# GPS.net
KiCad netlist of a schematic drawn in Altium Designer
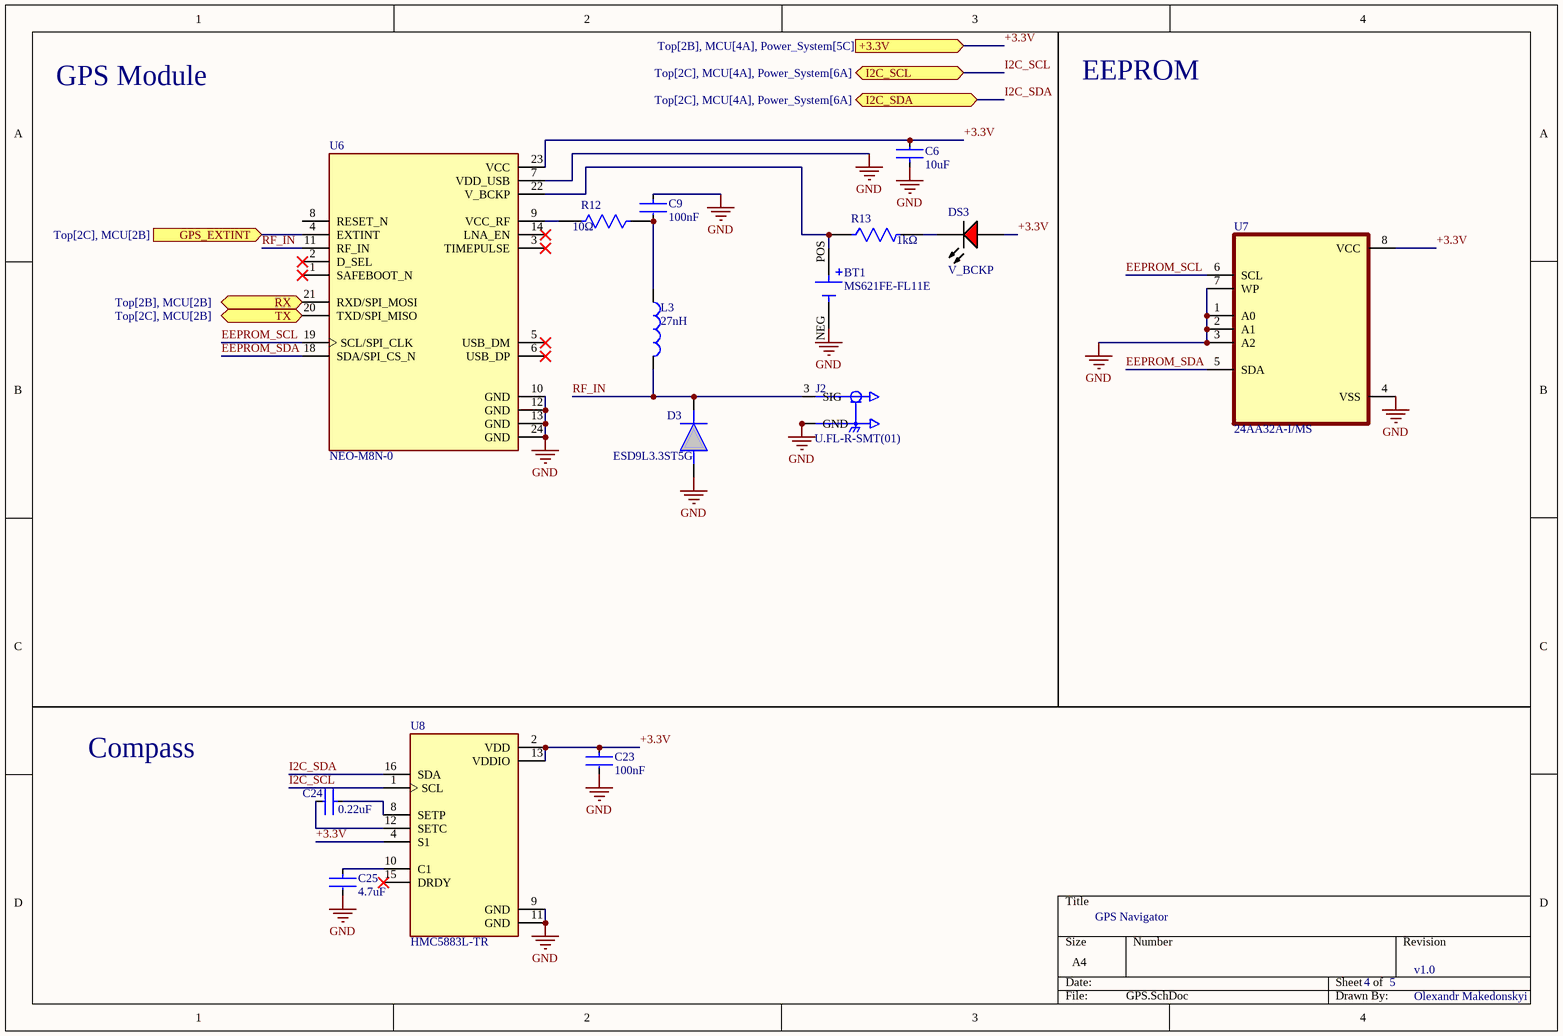
[diagram p0: GPS.SchDoc]

(export (version "E")
  (design (tool "Eeschema 10.0.6"))
  (components
    (comp (ref "BT1")
      (value "MS621FE-FL11E")
      (footprint "gps_project_pcb_library:BAT_MS621FE-FL11E")
      (description "Coin, 6.8mm 3 V Lithium Battery Rechargeable (Secondary) 5.5mAh")
      (fields (field (name "MF") "Seiko Instruments"))
      (libsource (lib "gps_project_schematic_library") (part "MS621FE-FL11E"))
    )
    (comp (ref "C6")
      (value "10uF")
      (footprint "0603_CAPACITOR")
      (libsource (lib "Olexandr Makedonskyi") (part "CAPACITOR"))
    )
    (comp (ref "C9")
      (value "100nF")
      (footprint "0603_CAPACITOR")
      (libsource (lib "Olexandr Makedonskyi") (part "CAPACITOR"))
    )
    (comp (ref "C23")
      (value "100nF")
      (footprint "0402_CAPACITOR")
      (libsource (lib "Olexandr Makedonskyi") (part "CAPACITOR"))
    )
    (comp (ref "C24")
      (value "0.22uF")
      (footprint "0402_CAPACITOR")
      (libsource (lib "Olexandr Makedonskyi") (part "CAPACITOR"))
    )
    (comp (ref "C25")
      (value "4.7uF")
      (footprint "0402_CAPACITOR")
      (libsource (lib "Olexandr Makedonskyi") (part "CAPACITOR"))
    )
    (comp (ref "D3")
      (value "ESD9L3.3ST5G")
      (footprint "gps_project_pcb_library:DIOM1006X40N")
      (description "Transient Voltage Suppressors ESD Protection Diodes with UltraLow Capacitance")
      (fields (field (name "MOUSER PART NUMBER") "863-ESD9L3.3ST5G"))
      (libsource (lib "gps_project_schematic_library") (part "ESD9L3.3ST5G"))
    )
    (comp (ref "DS3")
      (value "V_BCKP")
      (footprint "gps_project_pcb_library:RED_LED_1206")
      (description "LED Red, 65 mW, -40 to 85 degC, 2-Pin SMD, RoHS, Tape and Reel")
      (fields (field (name "MANUFACTURER") "Lumex") (field (name "PART NO") "SML-LX1206IC-TR"))
      (libsource (lib "gps_project_schematic_library") (part "LED_RED_1206"))
    )
    (comp (ref "J2")
      (value "U.FL-R-SMT(01)")
      (footprint "gps_project_pcb_library:HRS_U.FL-R-SMT(01)")
      (fields (field (name "MF") "Hirose"))
      (libsource (lib "gps_project_schematic_library") (part "U.FL-R-SMT(01)"))
    )
    (comp (ref "L3")
      (value "27nH")
      (footprint "gps_project_pcb_library:27nH")
      (description "Inductor with Inductance: 27nH Tol. +/-5%, Package: 0402 _1005_")
      (fields (field (name "MP") "LQG15HS27NJ02D") (field (name "MF") "Murata"))
      (libsource (lib "gps_project_schematic_library") (part "27nH"))
    )
    (comp (ref "R12")
      (value "10Ω")
      (footprint "1206_RESISTOR")
      (libsource (lib "gps_project_schematic_library") (part "RESISTOR"))
    )
    (comp (ref "R13")
      (value "1kΩ")
      (footprint "gps_project_pcb_library:0603_RESISTOR")
      (fields (field (name "Comment") "RESISTOR"))
      (libsource (lib "gps_project_schematic_library") (part "RESISTOR"))
    )
    (comp (ref "U6")
      (value "NEO-M8N-0")
      (footprint "gps_project_pcb_library:XCVR_NEO-M8N-0")
      (description "series RF Receiver BeiDou, Galileo, GLONASS, GNSS, GPS 1.575GHz -167dBm - - -")
      (fields (field (name "MF") "U-Blox America"))
      (libsource (lib "gps_project_schematic_library") (part "NEO-M8N-0"))
    )
    (comp (ref "U7")
      (value "24AA32A-I/MS")
      (footprint "gps_project_pcb_library:SOP65P490X110-8N (memory)")
      (description "32K, 4K X 8 1.8V SERIAL EE IND ¦ Microchip Technology Inc. 24AA32A-I/MS")
      (fields (field (name "MF") "Microchip"))
      (libsource (lib "gps_project_schematic_library") (part "24AA32A-I/MS"))
    )
    (comp (ref "U8")
      (value "HMC5883L-TR")
      (footprint "gps_project_pcb_library:XDCR_HMC5883L-TR")
      (fields (field (name "MF") "STMicroelectronics") (field (name "MP") "HMC5883LTR"))
      (libsource (lib "gps_project_schematic_library") (part "HMC5883L-TR"))
    )
  )
  (nets
    (net (code "1") (name "/+3.3V") (class "Default")
      (node (ref "C23") (pin "1") (pinfunction "1_1") (pintype "passive"))
      (node (ref "C6") (pin "2") (pinfunction "2_2") (pintype "passive"))
      (node (ref "DS3") (pin "1") (pinfunction "A_1") (pintype "passive"))
      (node (ref "U6") (pin "23") (pinfunction "VCC_23") (pintype "passive"))
      (node (ref "U7") (pin "8") (pinfunction "VCC_8") (pintype "passive"))
      (node (ref "U8") (pin "13") (pinfunction "VDDIO_13") (pintype "passive"))
      (node (ref "U8") (pin "2") (pinfunction "VDD_2") (pintype "passive"))
      (node (ref "U8") (pin "4") (pinfunction "S1_4") (pintype "passive"))
    )
    (net (code "2") (name "/EEPROM_SCL") (class "Default")
      (node (ref "U6") (pin "19") (pinfunction "SCL/SPI_CLK_19") (pintype "passive"))
      (node (ref "U7") (pin "6") (pinfunction "SCL_6") (pintype "passive"))
    )
    (net (code "3") (name "/EEPROM_SDA") (class "Default")
      (node (ref "U6") (pin "18") (pinfunction "SDA/SPI_CS_N_18") (pintype "passive"))
      (node (ref "U7") (pin "5") (pinfunction "SDA_5") (pintype "passive"))
    )
    (net (code "4") (name "/GPS_EXTINT") (class "Default")
      (node (ref "U6") (pin "4") (pinfunction "EXTINT_4") (pintype "passive"))
    )
    (net (code "5") (name "/I2C_SCL") (class "Default")
      (node (ref "U8") (pin "1") (pinfunction "SCL_1") (pintype "passive"))
    )
    (net (code "6") (name "/I2C_SDA") (class "Default")
      (node (ref "U8") (pin "16") (pinfunction "SDA_16") (pintype "passive"))
    )
    (net (code "7") (name "/RF_IN") (class "Default")
      (node (ref "D3") (pin "1") (pinfunction "K_1") (pintype "passive"))
      (node (ref "J2") (pin "3") (pinfunction "SIG_3") (pintype "passive"))
      (node (ref "L3") (pin "2") (pinfunction "2_2") (pintype "passive"))
      (node (ref "U6") (pin "11") (pinfunction "RF_IN_11") (pintype "passive"))
    )
    (net (code "8") (name "/RX") (class "Default")
      (node (ref "U6") (pin "21") (pinfunction "RXD/SPI_MOSI_21") (pintype "passive"))
    )
    (net (code "9") (name "/TX") (class "Default")
      (node (ref "U6") (pin "20") (pinfunction "TXD/SPI_MISO_20") (pintype "passive"))
    )
    (net (code "10") (name "GND") (class "Default")
      (node (ref "BT1") (pin "NEG") (pinfunction "NEG_NEG") (pintype "passive"))
      (node (ref "C23") (pin "2") (pinfunction "2_2") (pintype "passive"))
      (node (ref "C25") (pin "2") (pinfunction "2_2") (pintype "passive"))
      (node (ref "C6") (pin "1") (pinfunction "1_1") (pintype "passive"))
      (node (ref "C9") (pin "1") (pinfunction "1_1") (pintype "passive"))
      (node (ref "D3") (pin "2") (pinfunction "A_2") (pintype "passive"))
      (node (ref "J2") (pin "1") (pinfunction "GND_1") (pintype "passive"))
      (node (ref "J2") (pin "2") (pinfunction "GND_2") (pintype "passive"))
      (node (ref "U6") (pin "10") (pinfunction "GND_10") (pintype "passive"))
      (node (ref "U6") (pin "12") (pinfunction "GND_12") (pintype "passive"))
      (node (ref "U6") (pin "13") (pinfunction "GND_13") (pintype "passive"))
      (node (ref "U6") (pin "24") (pinfunction "GND_24") (pintype "passive"))
      (node (ref "U6") (pin "7") (pinfunction "VDD_USB_7") (pintype "passive"))
      (node (ref "U7") (pin "1") (pinfunction "A0_1") (pintype "passive"))
      (node (ref "U7") (pin "2") (pinfunction "A1_2") (pintype "passive"))
      (node (ref "U7") (pin "3") (pinfunction "A2_3") (pintype "passive"))
      (node (ref "U7") (pin "4") (pinfunction "VSS_4") (pintype "passive"))
      (node (ref "U7") (pin "7") (pinfunction "WP_7") (pintype "passive"))
      (node (ref "U8") (pin "11") (pinfunction "GND_11") (pintype "passive"))
      (node (ref "U8") (pin "9") (pinfunction "GND_9") (pintype "passive"))
    )
    (net (code "11") (name "Net-(C9-Pad2)") (class "Default")
      (node (ref "C9") (pin "2") (pinfunction "2_2") (pintype "passive"))
      (node (ref "L3") (pin "1") (pinfunction "1_1") (pintype "passive"))
      (node (ref "R12") (pin "1") (pinfunction "1_1") (pintype "passive"))
    )
    (net (code "12") (name "Net-(DS3-K)") (class "Default")
      (node (ref "DS3") (pin "2") (pinfunction "K_2") (pintype "passive"))
      (node (ref "R13") (pin "2") (pinfunction "2_2") (pintype "passive"))
    )
    (net (code "13") (name "Net-(U6-VCC_RF)") (class "Default")
      (node (ref "R12") (pin "2") (pinfunction "2_2") (pintype "passive"))
      (node (ref "U6") (pin "9") (pinfunction "VCC_RF_9") (pintype "passive"))
    )
    (net (code "14") (name "Net-(U6-V_BCKP)") (class "Default")
      (node (ref "BT1") (pin "POS") (pinfunction "POS_POS") (pintype "passive"))
      (node (ref "R13") (pin "1") (pinfunction "1_1") (pintype "passive"))
      (node (ref "U6") (pin "22") (pinfunction "V_BCKP_22") (pintype "passive"))
    )
    (net (code "15") (name "Net-(U8-C1)") (class "Default")
      (node (ref "C25") (pin "1") (pinfunction "1_1") (pintype "passive"))
      (node (ref "U8") (pin "10") (pinfunction "C1_10") (pintype "passive"))
    )
    (net (code "16") (name "Net-(U8-SETC)") (class "Default")
      (node (ref "C24") (pin "2") (pinfunction "2_2") (pintype "passive"))
      (node (ref "U8") (pin "12") (pinfunction "SETC_12") (pintype "passive"))
    )
    (net (code "17") (name "Net-(U8-SETP)") (class "Default")
      (node (ref "C24") (pin "1") (pinfunction "1_1") (pintype "passive"))
      (node (ref "U8") (pin "8") (pinfunction "SETP_8") (pintype "passive"))
    )
    (net (code "18") (name "unconnected-(U6-D_SEL-Pad2)") (class "Default")
      (node (ref "U6") (pin "2") (pinfunction "D_SEL_2") (pintype "passive+no_connect"))
    )
    (net (code "19") (name "unconnected-(U6-LNA_EN-Pad14)") (class "Default")
      (node (ref "U6") (pin "14") (pinfunction "LNA_EN_14") (pintype "passive+no_connect"))
    )
    (net (code "20") (name "unconnected-(U6-RESET_N-Pad8)") (class "Default")
      (node (ref "U6") (pin "8") (pinfunction "RESET_N_8") (pintype "passive"))
    )
    (net (code "21") (name "unconnected-(U6-SAFEBOOT_N-Pad1)") (class "Default")
      (node (ref "U6") (pin "1") (pinfunction "SAFEBOOT_N_1") (pintype "passive+no_connect"))
    )
    (net (code "22") (name "unconnected-(U6-TIMEPULSE-Pad3)") (class "Default")
      (node (ref "U6") (pin "3") (pinfunction "TIMEPULSE_3") (pintype "passive+no_connect"))
    )
    (net (code "23") (name "unconnected-(U6-USB_DM-Pad5)") (class "Default")
      (node (ref "U6") (pin "5") (pinfunction "USB_DM_5") (pintype "passive+no_connect"))
    )
    (net (code "24") (name "unconnected-(U6-USB_DP-Pad6)") (class "Default")
      (node (ref "U6") (pin "6") (pinfunction "USB_DP_6") (pintype "passive+no_connect"))
    )
    (net (code "25") (name "unconnected-(U8-DRDY-Pad15)") (class "Default")
      (node (ref "U8") (pin "15") (pinfunction "DRDY_15") (pintype "passive+no_connect"))
    )
  )
)
